# macrokeyboard_2020-07-03_19-43-42.net
KiCad netlist of a schematic drawn in EasyEDA
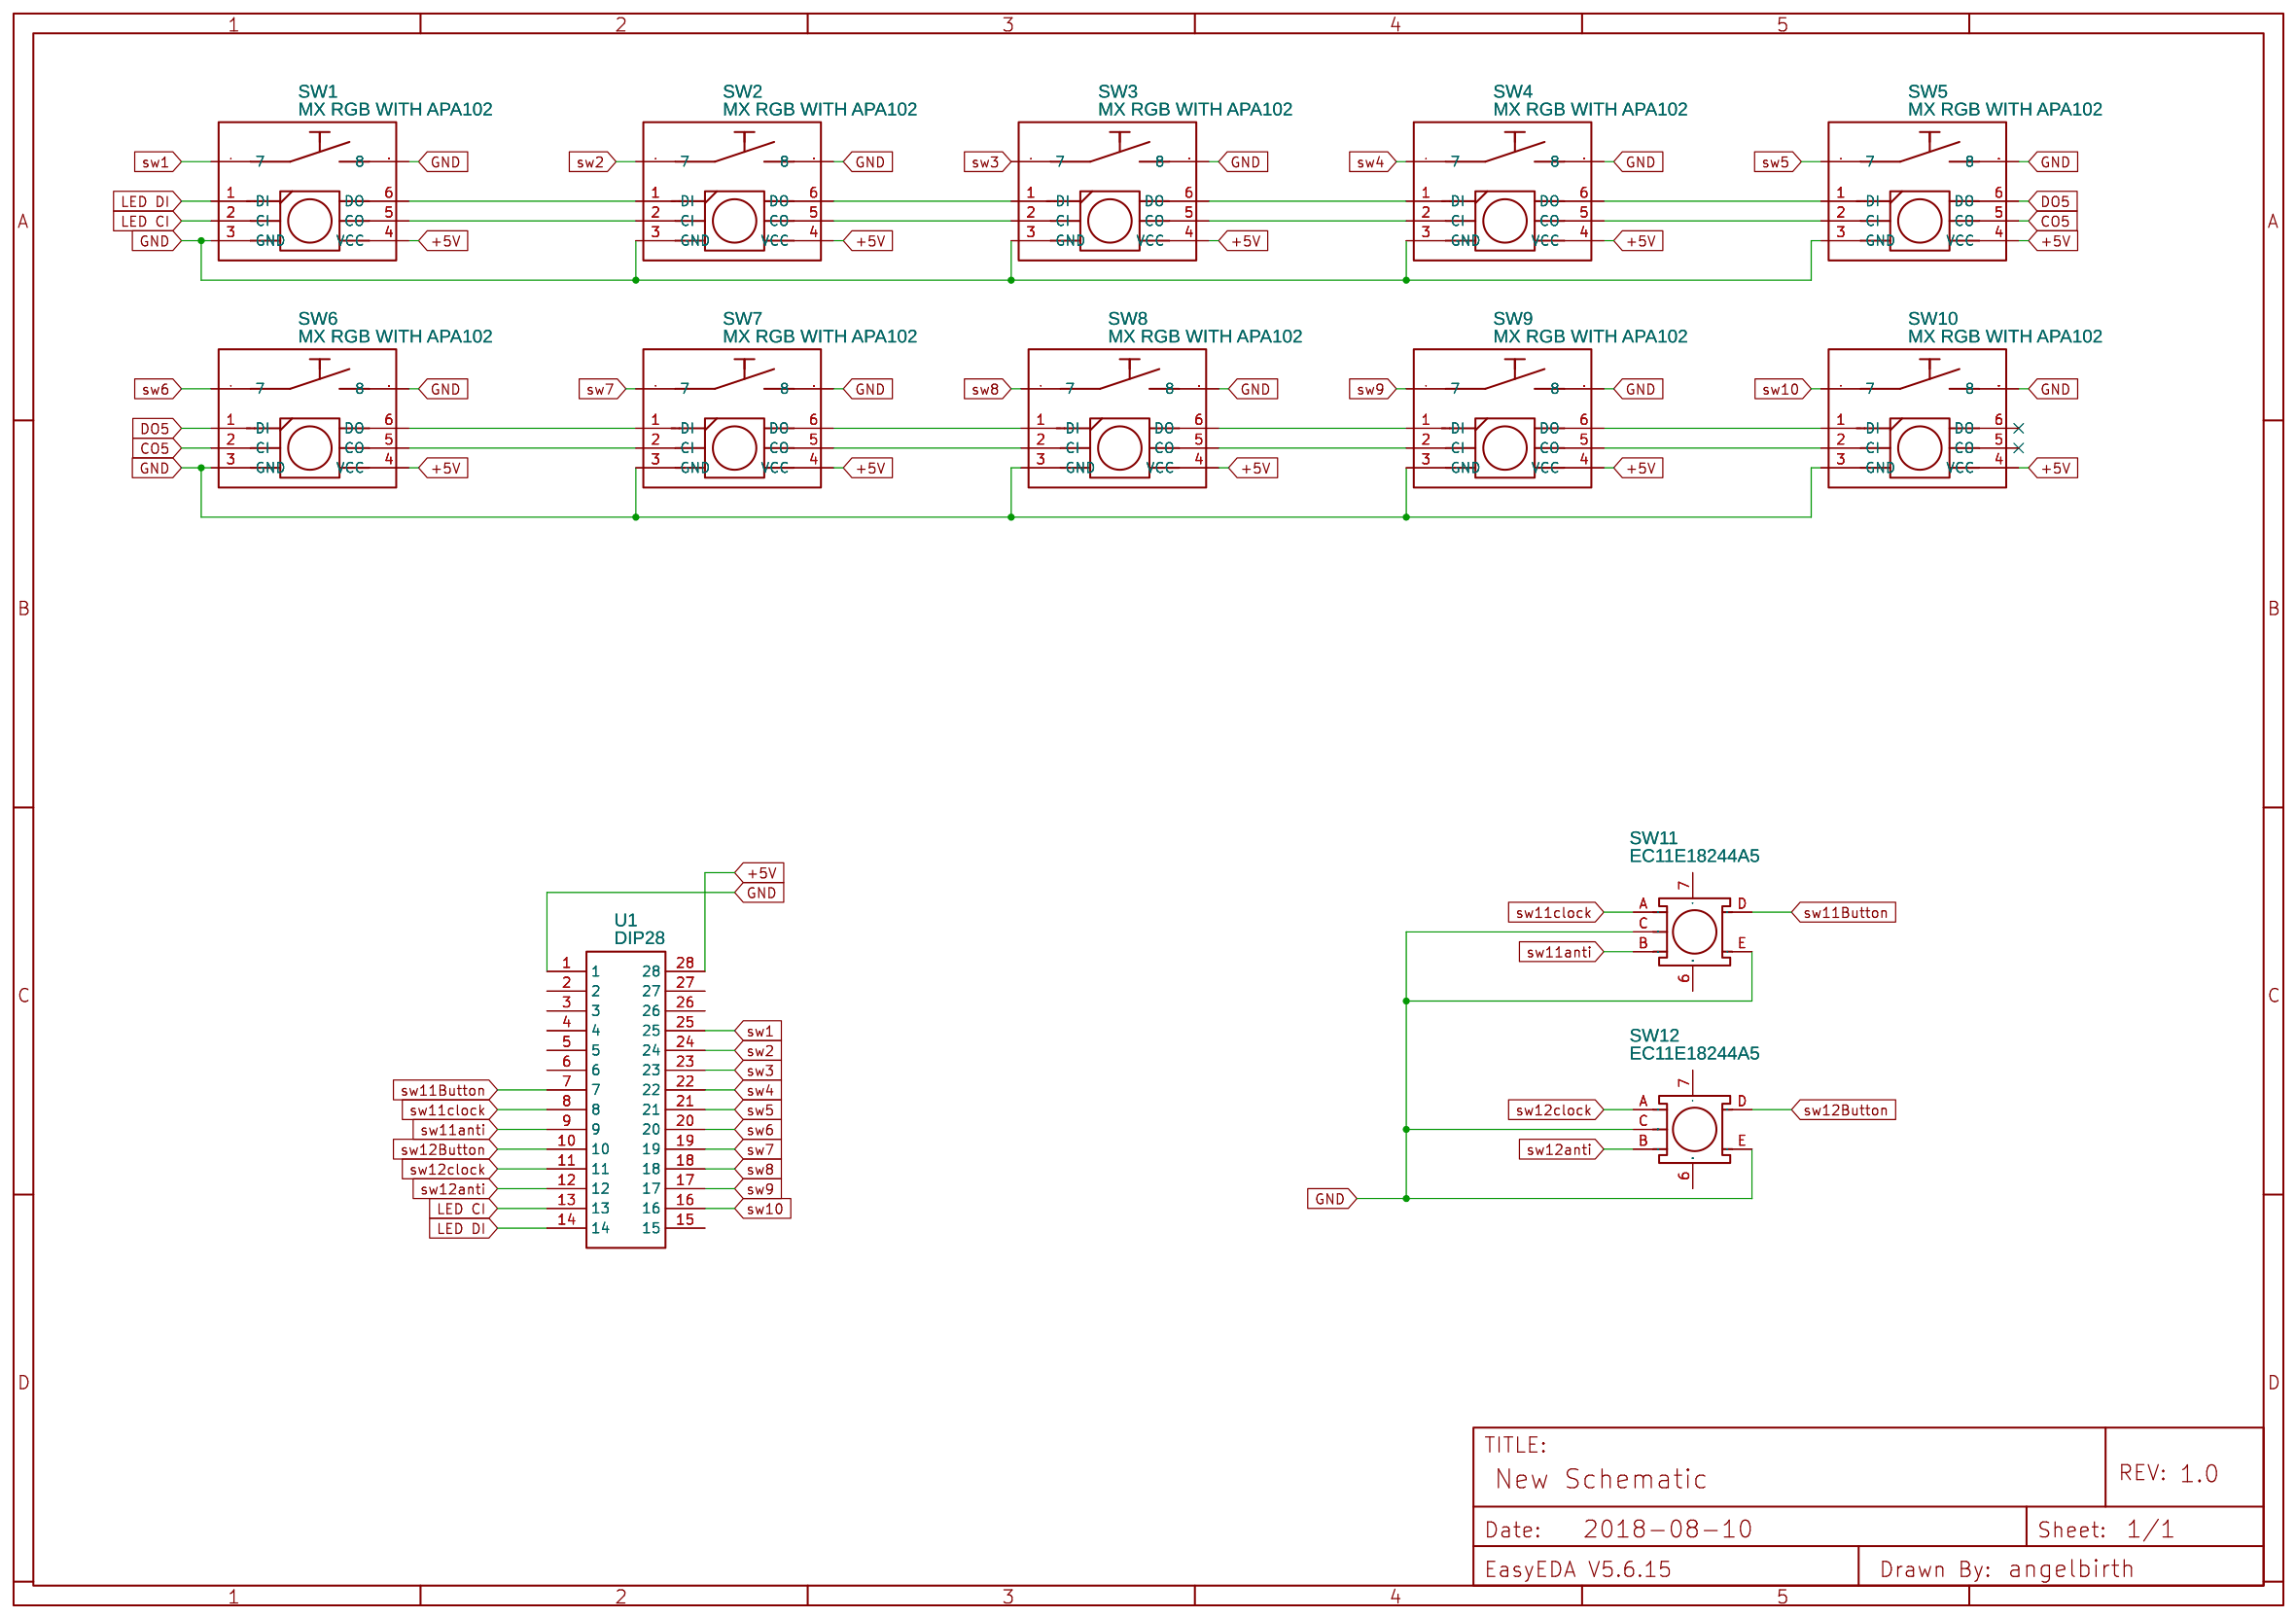
[diagram p0: schematic sheet]

(export (version "E")
  (design (tool "Eeschema 10.0.6"))
  (components
    (comp (ref "SW1") (value "MX RGB WITH APA102") (libsource (lib "") (part "MX RGB WITH APA102")))
    (comp (ref "SW2") (value "MX RGB WITH APA102") (libsource (lib "") (part "MX RGB WITH APA102")))
    (comp (ref "SW3") (value "MX RGB WITH APA102") (libsource (lib "") (part "MX RGB WITH APA102")))
    (comp (ref "SW4") (value "MX RGB WITH APA102") (libsource (lib "") (part "MX RGB WITH APA102")))
    (comp (ref "SW5") (value "MX RGB WITH APA102") (libsource (lib "") (part "MX RGB WITH APA102")))
    (comp (ref "SW6") (value "MX RGB WITH APA102") (libsource (lib "") (part "MX RGB WITH APA102")))
    (comp (ref "SW7") (value "MX RGB WITH APA102") (libsource (lib "") (part "MX RGB WITH APA102")))
    (comp (ref "SW8") (value "MX RGB WITH APA102") (libsource (lib "") (part "MX RGB WITH APA102")))
    (comp (ref "SW9") (value "MX RGB WITH APA102") (libsource (lib "") (part "MX RGB WITH APA102")))
    (comp (ref "SW10") (value "MX RGB WITH APA102") (libsource (lib "") (part "MX RGB WITH APA102")))
    (comp (ref "SW11")
      (value "EC11E18244A5")
      (fields (field (name "BOM_Supplier Part") "C255515"))
      (libsource (lib "") (part "EC11E18244A5"))
    )
    (comp (ref "SW12")
      (value "EC11E18244A5")
      (fields (field (name "BOM_Supplier Part") "C255515"))
      (libsource (lib "") (part "EC11E18244A5"))
    )
    (comp (ref "U1") (value "DIP28") (libsource (lib "") (part "DIP28")))
  )
  (nets
    (net (code "1") (name "+5V") (class "Default")
      (node (ref "SW1") (pin "4") (pinfunction "VCC_4") (pintype "unspecified"))
      (node (ref "SW10") (pin "4") (pinfunction "VCC_4") (pintype "unspecified"))
      (node (ref "SW2") (pin "4") (pinfunction "VCC_4") (pintype "unspecified"))
      (node (ref "SW3") (pin "4") (pinfunction "VCC_4") (pintype "unspecified"))
      (node (ref "SW4") (pin "4") (pinfunction "VCC_4") (pintype "unspecified"))
      (node (ref "SW5") (pin "4") (pinfunction "VCC_4") (pintype "unspecified"))
      (node (ref "SW6") (pin "4") (pinfunction "VCC_4") (pintype "unspecified"))
      (node (ref "SW7") (pin "4") (pinfunction "VCC_4") (pintype "unspecified"))
      (node (ref "SW8") (pin "4") (pinfunction "VCC_4") (pintype "unspecified"))
      (node (ref "SW9") (pin "4") (pinfunction "VCC_4") (pintype "unspecified"))
      (node (ref "U1") (pin "28") (pinfunction "28_28") (pintype "unspecified"))
    )
    (net (code "2") (name "CO5") (class "Default")
      (node (ref "SW5") (pin "5") (pinfunction "CO_5") (pintype "unspecified"))
      (node (ref "SW6") (pin "2") (pinfunction "CI_2") (pintype "unspecified"))
    )
    (net (code "3") (name "DO5") (class "Default")
      (node (ref "SW5") (pin "6") (pinfunction "DO_6") (pintype "unspecified"))
      (node (ref "SW6") (pin "1") (pinfunction "DI_1") (pintype "unspecified"))
    )
    (net (code "4") (name "GND") (class "Default")
      (node (ref "SW1") (pin "3") (pinfunction "GND_3") (pintype "unspecified"))
      (node (ref "SW1") (pin "8") (pinfunction "8_8") (pintype "unspecified"))
      (node (ref "SW10") (pin "3") (pinfunction "GND_3") (pintype "unspecified"))
      (node (ref "SW10") (pin "8") (pinfunction "8_8") (pintype "unspecified"))
      (node (ref "SW11") (pin "C") (pinfunction "C_C") (pintype "unspecified"))
      (node (ref "SW11") (pin "E") (pinfunction "E_E") (pintype "unspecified"))
      (node (ref "SW12") (pin "C") (pinfunction "C_C") (pintype "unspecified"))
      (node (ref "SW12") (pin "E") (pinfunction "E_E") (pintype "unspecified"))
      (node (ref "SW2") (pin "3") (pinfunction "GND_3") (pintype "unspecified"))
      (node (ref "SW2") (pin "8") (pinfunction "8_8") (pintype "unspecified"))
      (node (ref "SW3") (pin "3") (pinfunction "GND_3") (pintype "unspecified"))
      (node (ref "SW3") (pin "8") (pinfunction "8_8") (pintype "unspecified"))
      (node (ref "SW4") (pin "3") (pinfunction "GND_3") (pintype "unspecified"))
      (node (ref "SW4") (pin "8") (pinfunction "8_8") (pintype "unspecified"))
      (node (ref "SW5") (pin "3") (pinfunction "GND_3") (pintype "unspecified"))
      (node (ref "SW5") (pin "8") (pinfunction "8_8") (pintype "unspecified"))
      (node (ref "SW6") (pin "3") (pinfunction "GND_3") (pintype "unspecified"))
      (node (ref "SW6") (pin "8") (pinfunction "8_8") (pintype "unspecified"))
      (node (ref "SW7") (pin "3") (pinfunction "GND_3") (pintype "unspecified"))
      (node (ref "SW7") (pin "8") (pinfunction "8_8") (pintype "unspecified"))
      (node (ref "SW8") (pin "3") (pinfunction "GND_3") (pintype "unspecified"))
      (node (ref "SW8") (pin "8") (pinfunction "8_8") (pintype "unspecified"))
      (node (ref "SW9") (pin "3") (pinfunction "GND_3") (pintype "unspecified"))
      (node (ref "SW9") (pin "8") (pinfunction "8_8") (pintype "unspecified"))
      (node (ref "U1") (pin "1") (pinfunction "1_1") (pintype "unspecified"))
    )
    (net (code "5") (name "LED CI") (class "Default")
      (node (ref "SW1") (pin "2") (pinfunction "CI_2") (pintype "unspecified"))
      (node (ref "U1") (pin "13") (pinfunction "13_13") (pintype "unspecified"))
    )
    (net (code "6") (name "LED DI") (class "Default")
      (node (ref "SW1") (pin "1") (pinfunction "DI_1") (pintype "unspecified"))
      (node (ref "U1") (pin "14") (pinfunction "14_14") (pintype "unspecified"))
    )
    (net (code "7") (name "Net-(SW1-CO)") (class "Default")
      (node (ref "SW1") (pin "5") (pinfunction "CO_5") (pintype "unspecified"))
      (node (ref "SW2") (pin "2") (pinfunction "CI_2") (pintype "unspecified"))
    )
    (net (code "8") (name "Net-(SW1-DO)") (class "Default")
      (node (ref "SW1") (pin "6") (pinfunction "DO_6") (pintype "unspecified"))
      (node (ref "SW2") (pin "1") (pinfunction "DI_1") (pintype "unspecified"))
    )
    (net (code "9") (name "Net-(SW2-CO)") (class "Default")
      (node (ref "SW2") (pin "5") (pinfunction "CO_5") (pintype "unspecified"))
      (node (ref "SW3") (pin "2") (pinfunction "CI_2") (pintype "unspecified"))
    )
    (net (code "10") (name "Net-(SW2-DO)") (class "Default")
      (node (ref "SW2") (pin "6") (pinfunction "DO_6") (pintype "unspecified"))
      (node (ref "SW3") (pin "1") (pinfunction "DI_1") (pintype "unspecified"))
    )
    (net (code "11") (name "Net-(SW3-CO)") (class "Default")
      (node (ref "SW3") (pin "5") (pinfunction "CO_5") (pintype "unspecified"))
      (node (ref "SW4") (pin "2") (pinfunction "CI_2") (pintype "unspecified"))
    )
    (net (code "12") (name "Net-(SW3-DO)") (class "Default")
      (node (ref "SW3") (pin "6") (pinfunction "DO_6") (pintype "unspecified"))
      (node (ref "SW4") (pin "1") (pinfunction "DI_1") (pintype "unspecified"))
    )
    (net (code "13") (name "Net-(SW4-CO)") (class "Default")
      (node (ref "SW4") (pin "5") (pinfunction "CO_5") (pintype "unspecified"))
      (node (ref "SW5") (pin "2") (pinfunction "CI_2") (pintype "unspecified"))
    )
    (net (code "14") (name "Net-(SW4-DO)") (class "Default")
      (node (ref "SW4") (pin "6") (pinfunction "DO_6") (pintype "unspecified"))
      (node (ref "SW5") (pin "1") (pinfunction "DI_1") (pintype "unspecified"))
    )
    (net (code "15") (name "Net-(SW6-CO)") (class "Default")
      (node (ref "SW6") (pin "5") (pinfunction "CO_5") (pintype "unspecified"))
      (node (ref "SW7") (pin "2") (pinfunction "CI_2") (pintype "unspecified"))
    )
    (net (code "16") (name "Net-(SW6-DO)") (class "Default")
      (node (ref "SW6") (pin "6") (pinfunction "DO_6") (pintype "unspecified"))
      (node (ref "SW7") (pin "1") (pinfunction "DI_1") (pintype "unspecified"))
    )
    (net (code "17") (name "Net-(SW7-CO)") (class "Default")
      (node (ref "SW7") (pin "5") (pinfunction "CO_5") (pintype "unspecified"))
      (node (ref "SW8") (pin "2") (pinfunction "CI_2") (pintype "unspecified"))
    )
    (net (code "18") (name "Net-(SW7-DO)") (class "Default")
      (node (ref "SW7") (pin "6") (pinfunction "DO_6") (pintype "unspecified"))
      (node (ref "SW8") (pin "1") (pinfunction "DI_1") (pintype "unspecified"))
    )
    (net (code "19") (name "Net-(SW8-CO)") (class "Default")
      (node (ref "SW8") (pin "5") (pinfunction "CO_5") (pintype "unspecified"))
      (node (ref "SW9") (pin "2") (pinfunction "CI_2") (pintype "unspecified"))
    )
    (net (code "20") (name "Net-(SW8-DO)") (class "Default")
      (node (ref "SW8") (pin "6") (pinfunction "DO_6") (pintype "unspecified"))
      (node (ref "SW9") (pin "1") (pinfunction "DI_1") (pintype "unspecified"))
    )
    (net (code "21") (name "Net-(SW10-CI)") (class "Default")
      (node (ref "SW10") (pin "2") (pinfunction "CI_2") (pintype "unspecified"))
      (node (ref "SW9") (pin "5") (pinfunction "CO_5") (pintype "unspecified"))
    )
    (net (code "22") (name "Net-(SW10-DI)") (class "Default")
      (node (ref "SW10") (pin "1") (pinfunction "DI_1") (pintype "unspecified"))
      (node (ref "SW9") (pin "6") (pinfunction "DO_6") (pintype "unspecified"))
    )
    (net (code "23") (name "sw1") (class "Default")
      (node (ref "SW1") (pin "7") (pinfunction "7_7") (pintype "unspecified"))
      (node (ref "U1") (pin "25") (pinfunction "25_25") (pintype "unspecified"))
    )
    (net (code "24") (name "sw2") (class "Default")
      (node (ref "SW2") (pin "7") (pinfunction "7_7") (pintype "unspecified"))
      (node (ref "U1") (pin "24") (pinfunction "24_24") (pintype "unspecified"))
    )
    (net (code "25") (name "sw3") (class "Default")
      (node (ref "SW3") (pin "7") (pinfunction "7_7") (pintype "unspecified"))
      (node (ref "U1") (pin "23") (pinfunction "23_23") (pintype "unspecified"))
    )
    (net (code "26") (name "sw4") (class "Default")
      (node (ref "SW4") (pin "7") (pinfunction "7_7") (pintype "unspecified"))
      (node (ref "U1") (pin "22") (pinfunction "22_22") (pintype "unspecified"))
    )
    (net (code "27") (name "sw5") (class "Default")
      (node (ref "SW5") (pin "7") (pinfunction "7_7") (pintype "unspecified"))
      (node (ref "U1") (pin "21") (pinfunction "21_21") (pintype "unspecified"))
    )
    (net (code "28") (name "sw6") (class "Default")
      (node (ref "SW6") (pin "7") (pinfunction "7_7") (pintype "unspecified"))
      (node (ref "U1") (pin "20") (pinfunction "20_20") (pintype "unspecified"))
    )
    (net (code "29") (name "sw7") (class "Default")
      (node (ref "SW7") (pin "7") (pinfunction "7_7") (pintype "unspecified"))
      (node (ref "U1") (pin "19") (pinfunction "19_19") (pintype "unspecified"))
    )
    (net (code "30") (name "sw8") (class "Default")
      (node (ref "SW8") (pin "7") (pinfunction "7_7") (pintype "unspecified"))
      (node (ref "U1") (pin "18") (pinfunction "18_18") (pintype "unspecified"))
    )
    (net (code "31") (name "sw9") (class "Default")
      (node (ref "SW9") (pin "7") (pinfunction "7_7") (pintype "unspecified"))
      (node (ref "U1") (pin "17") (pinfunction "17_17") (pintype "unspecified"))
    )
    (net (code "32") (name "sw10") (class "Default")
      (node (ref "SW10") (pin "7") (pinfunction "7_7") (pintype "unspecified"))
      (node (ref "U1") (pin "16") (pinfunction "16_16") (pintype "unspecified"))
    )
    (net (code "33") (name "sw11Button") (class "Default")
      (node (ref "SW11") (pin "D") (pinfunction "D_D") (pintype "unspecified"))
      (node (ref "U1") (pin "7") (pinfunction "7_7") (pintype "unspecified"))
    )
    (net (code "34") (name "sw11anti") (class "Default")
      (node (ref "SW11") (pin "B") (pinfunction "B_B") (pintype "unspecified"))
      (node (ref "U1") (pin "9") (pinfunction "9_9") (pintype "unspecified"))
    )
    (net (code "35") (name "sw11clock") (class "Default")
      (node (ref "SW11") (pin "A") (pinfunction "A_A") (pintype "unspecified"))
      (node (ref "U1") (pin "8") (pinfunction "8_8") (pintype "unspecified"))
    )
    (net (code "36") (name "sw12Button") (class "Default")
      (node (ref "SW12") (pin "D") (pinfunction "D_D") (pintype "unspecified"))
      (node (ref "U1") (pin "10") (pinfunction "10_10") (pintype "unspecified"))
    )
    (net (code "37") (name "sw12anti") (class "Default")
      (node (ref "SW12") (pin "B") (pinfunction "B_B") (pintype "unspecified"))
      (node (ref "U1") (pin "12") (pinfunction "12_12") (pintype "unspecified"))
    )
    (net (code "38") (name "sw12clock") (class "Default")
      (node (ref "SW12") (pin "A") (pinfunction "A_A") (pintype "unspecified"))
      (node (ref "U1") (pin "11") (pinfunction "11_11") (pintype "unspecified"))
    )
    (net (code "39") (name "unconnected-(SW10-CO-Pad5)") (class "Default")
      (node (ref "SW10") (pin "5") (pinfunction "CO_5") (pintype "unspecified+no_connect"))
    )
    (net (code "40") (name "unconnected-(SW10-DO-Pad6)") (class "Default")
      (node (ref "SW10") (pin "6") (pinfunction "DO_6") (pintype "unspecified+no_connect"))
    )
    (net (code "41") (name "unconnected-(SW11-Pad6)") (class "Default")
      (node (ref "SW11") (pin "6") (pinfunction "6_6") (pintype "unspecified"))
    )
    (net (code "42") (name "unconnected-(SW11-Pad7)") (class "Default")
      (node (ref "SW11") (pin "7") (pinfunction "7_7") (pintype "unspecified"))
    )
    (net (code "43") (name "unconnected-(SW12-Pad6)") (class "Default")
      (node (ref "SW12") (pin "6") (pinfunction "6_6") (pintype "unspecified"))
    )
    (net (code "44") (name "unconnected-(SW12-Pad7)") (class "Default")
      (node (ref "SW12") (pin "7") (pinfunction "7_7") (pintype "unspecified"))
    )
    (net (code "45") (name "unconnected-(U1-Pad2)") (class "Default")
      (node (ref "U1") (pin "2") (pinfunction "2_2") (pintype "unspecified"))
    )
    (net (code "46") (name "unconnected-(U1-Pad3)") (class "Default")
      (node (ref "U1") (pin "3") (pinfunction "3_3") (pintype "unspecified"))
    )
    (net (code "47") (name "unconnected-(U1-Pad4)") (class "Default")
      (node (ref "U1") (pin "4") (pinfunction "4_4") (pintype "unspecified"))
    )
    (net (code "48") (name "unconnected-(U1-Pad5)") (class "Default")
      (node (ref "U1") (pin "5") (pinfunction "5_5") (pintype "unspecified"))
    )
    (net (code "49") (name "unconnected-(U1-Pad6)") (class "Default")
      (node (ref "U1") (pin "6") (pinfunction "6_6") (pintype "unspecified"))
    )
    (net (code "50") (name "unconnected-(U1-Pad15)") (class "Default")
      (node (ref "U1") (pin "15") (pinfunction "15_15") (pintype "unspecified"))
    )
    (net (code "51") (name "unconnected-(U1-Pad26)") (class "Default")
      (node (ref "U1") (pin "26") (pinfunction "26_26") (pintype "unspecified"))
    )
    (net (code "52") (name "unconnected-(U1-Pad27)") (class "Default")
      (node (ref "U1") (pin "27") (pinfunction "27_27") (pintype "unspecified"))
    )
  )
)
